# Sheet5.net
KiCad netlist of a schematic drawn in Altium Designer
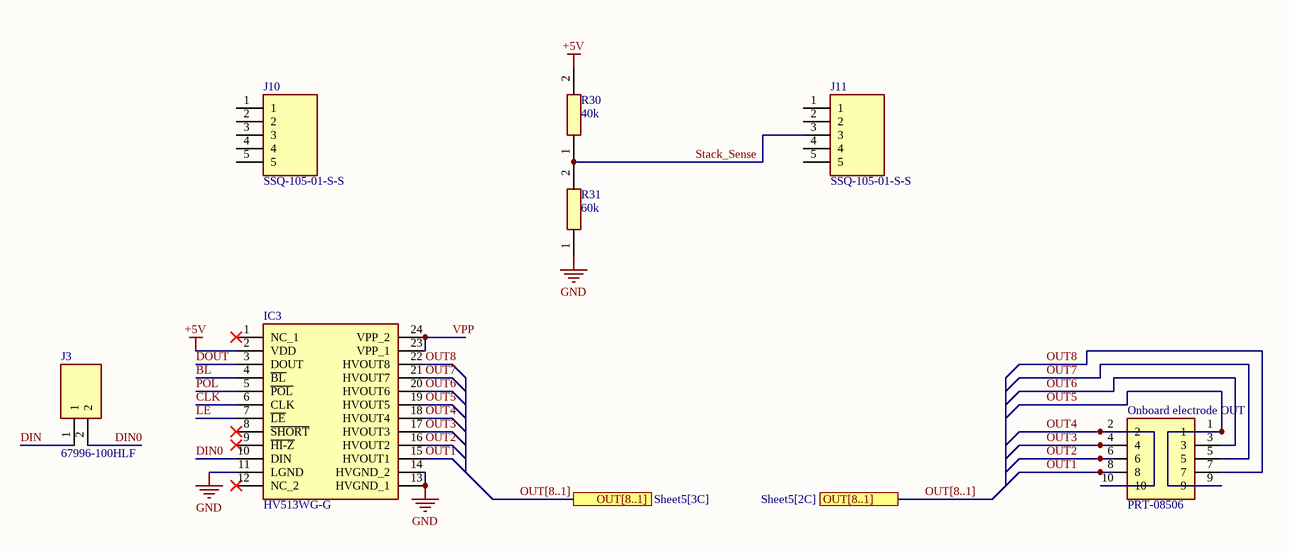
[diagram p0: Sheet5.SchDoc]

(export (version "E")
  (design (tool "Eeschema 10.0.6"))
  (components
    (comp (ref "IC3")
      (value "HV513WG-G")
      (footprint "SamacSys:SOIC127P1030X265-24N")
      (description "Integrated Circuit")
      (fields (field (name "MOUSER PART NUMBER") "689-HV513WG-G"))
      (libsource (lib "*") (part "HV513WG-G"))
    )
    (comp (ref "J3")
      (value "67996-100HLF")
      (footprint "HDRV2W67P254_2X1_254X483X858P")
      (libsource (lib "67996-100HLF") (part "67996-100HLF"))
    )
    (comp (ref "J10")
      (value "SSQ-105-01-S-S")
      (footprint "RHDR5W64P254_1X5_1321X241X851P")
      (description "5 Position, .100&quot; Tiger Buy&trade; Socket Strip, Square Tail, Single Row")
      (fields (field (name "MOUSER PART NUMBER") "200-SSQ10501SS"))
      (libsource (lib "SSQ-105-01-S-S") (part "SSQ-105-01-S-S"))
    )
    (comp (ref "J11")
      (value "SSQ-105-01-S-S")
      (footprint "RHDR5W64P254_1X5_1321X241X851P")
      (description "5 Position, .100&quot; Tiger Buy&trade; Socket Strip, Square Tail, Single Row")
      (fields (field (name "MOUSER PART NUMBER") "200-SSQ10501SS"))
      (libsource (lib "SSQ-105-01-S-S") (part "SSQ-105-01-S-S"))
    )
    (comp (ref "Onboard electrode OUT")
      (value "PRT-08506")
      (footprint "SamacSys:SHDR10W64P254_2X5_2025X900X935P")
      (description "Connector")
      (fields (field (name "MOUSER PART NUMBER") "474-PRT-08506"))
      (libsource (lib "*") (part "PRT-08506"))
    )
    (comp (ref "R30")
      (value "40k")
      (footprint "SamacSys:ERJP06D1000V")
      (description "Resistor")
      (fields
        (field (name "MANUFACTURER_PART_NUMBER") "ERJ-P06F5103V")
        (field (name "MOUSER PART NUMBER") "667-ERJ-P06F5103V")
      )
      (libsource (lib "SamacSys") (part "ERJ-P06F5103V"))
    )
    (comp (ref "R31")
      (value "60k")
      (footprint "SamacSys:ERJP06D1000V")
      (description "Resistor")
      (fields
        (field (name "MANUFACTURER_PART_NUMBER") "ERJ-P06F5103V")
        (field (name "MOUSER PART NUMBER") "667-ERJ-P06F5103V")
      )
      (libsource (lib "SamacSys") (part "ERJ-P06F5103V"))
    )
  )
  (nets
    (net (code "1") (name "+5V") (class "Default")
      (node (ref "IC3") (pin "2") (pinfunction "VDD_2") (pintype "passive"))
      (node (ref "R30") (pin "2") (pinfunction "2_2") (pintype "passive"))
    )
    (net (code "2") (name "/BL") (class "Default")
      (node (ref "IC3") (pin "4") (pinfunction "~{BL}_4") (pintype "passive"))
    )
    (net (code "3") (name "/CLK") (class "Default")
      (node (ref "IC3") (pin "6") (pinfunction "CLK_6") (pintype "passive"))
    )
    (net (code "4") (name "/DIN") (class "Default")
      (node (ref "J3") (pin "1") (pinfunction "1_1") (pintype "passive"))
    )
    (net (code "5") (name "/DIN0") (class "Default")
      (node (ref "IC3") (pin "10") (pinfunction "DIN_10") (pintype "passive"))
      (node (ref "J3") (pin "2") (pinfunction "2_2") (pintype "passive"))
    )
    (net (code "6") (name "/DOUT") (class "Default")
      (node (ref "IC3") (pin "3") (pinfunction "DOUT_3") (pintype "passive"))
    )
    (net (code "7") (name "/LE") (class "Default")
      (node (ref "IC3") (pin "7") (pinfunction "~{LE}_7") (pintype "passive"))
    )
    (net (code "8") (name "/OUT1") (class "Default")
      (node (ref "IC3") (pin "15") (pinfunction "HVOUT1_15") (pintype "passive"))
      (node (ref "Onboard electrode OUT") (pin "8") (pinfunction "8_8") (pintype "passive"))
    )
    (net (code "9") (name "/OUT2") (class "Default")
      (node (ref "IC3") (pin "16") (pinfunction "HVOUT2_16") (pintype "passive"))
      (node (ref "Onboard electrode OUT") (pin "6") (pinfunction "6_6") (pintype "passive"))
    )
    (net (code "10") (name "/OUT3") (class "Default")
      (node (ref "IC3") (pin "17") (pinfunction "HVOUT3_17") (pintype "passive"))
      (node (ref "Onboard electrode OUT") (pin "4") (pinfunction "4_4") (pintype "passive"))
    )
    (net (code "11") (name "/OUT4") (class "Default")
      (node (ref "IC3") (pin "18") (pinfunction "HVOUT4_18") (pintype "passive"))
      (node (ref "Onboard electrode OUT") (pin "10") (pinfunction "10_10") (pintype "passive"))
      (node (ref "Onboard electrode OUT") (pin "2") (pinfunction "2_2") (pintype "passive"))
    )
    (net (code "12") (name "/OUT5") (class "Default")
      (node (ref "IC3") (pin "19") (pinfunction "HVOUT5_19") (pintype "passive"))
      (node (ref "Onboard electrode OUT") (pin "1") (pinfunction "1_1") (pintype "passive"))
      (node (ref "Onboard electrode OUT") (pin "9") (pinfunction "9_9") (pintype "passive"))
    )
    (net (code "13") (name "/OUT6") (class "Default")
      (node (ref "IC3") (pin "20") (pinfunction "HVOUT6_20") (pintype "passive"))
      (node (ref "Onboard electrode OUT") (pin "3") (pinfunction "3_3") (pintype "passive"))
    )
    (net (code "14") (name "/OUT7") (class "Default")
      (node (ref "IC3") (pin "21") (pinfunction "HVOUT7_21") (pintype "passive"))
      (node (ref "Onboard electrode OUT") (pin "5") (pinfunction "5_5") (pintype "passive"))
    )
    (net (code "15") (name "/OUT8") (class "Default")
      (node (ref "IC3") (pin "22") (pinfunction "HVOUT8_22") (pintype "passive"))
      (node (ref "Onboard electrode OUT") (pin "7") (pinfunction "7_7") (pintype "passive"))
    )
    (net (code "17") (name "/POL") (class "Default")
      (node (ref "IC3") (pin "5") (pinfunction "~{POL}_5") (pintype "passive"))
    )
    (net (code "18") (name "/Stack_Sense") (class "Default")
      (node (ref "J11") (pin "3") (pinfunction "3_3") (pintype "passive"))
      (node (ref "R30") (pin "1") (pinfunction "1_1") (pintype "passive"))
      (node (ref "R31") (pin "2") (pinfunction "2_2") (pintype "passive"))
    )
    (net (code "19") (name "/VPP") (class "Default")
      (node (ref "IC3") (pin "23") (pinfunction "VPP_1_23") (pintype "passive"))
      (node (ref "IC3") (pin "24") (pinfunction "VPP_2_24") (pintype "passive"))
    )
    (net (code "20") (name "GND") (class "Default")
      (node (ref "IC3") (pin "11") (pinfunction "LGND_11") (pintype "passive"))
      (node (ref "IC3") (pin "13") (pinfunction "HVGND_1_13") (pintype "passive"))
      (node (ref "IC3") (pin "14") (pinfunction "HVGND_2_14") (pintype "passive"))
      (node (ref "R31") (pin "1") (pinfunction "1_1") (pintype "passive"))
    )
    (net (code "21") (name "unconnected-(IC3-NC_1-Pad1)") (class "Default")
      (node (ref "IC3") (pin "1") (pinfunction "NC_1_1") (pintype "passive+no_connect"))
    )
    (net (code "22") (name "unconnected-(IC3-NC_2-Pad12)") (class "Default")
      (node (ref "IC3") (pin "12") (pinfunction "NC_2_12") (pintype "passive+no_connect"))
    )
    (net (code "23") (name "unconnected-(IC3-~{HI-Z}-Pad9)") (class "Default")
      (node (ref "IC3") (pin "9") (pinfunction "~{HI-Z}_9") (pintype "passive+no_connect"))
    )
    (net (code "24") (name "unconnected-(IC3-~{SHORT}-Pad8)") (class "Default")
      (node (ref "IC3") (pin "8") (pinfunction "~{SHORT}_8") (pintype "passive+no_connect"))
    )
    (net (code "25") (name "unconnected-(J10-Pad1)") (class "Default")
      (node (ref "J10") (pin "1") (pinfunction "1_1") (pintype "passive"))
    )
    (net (code "26") (name "unconnected-(J10-Pad2)") (class "Default")
      (node (ref "J10") (pin "2") (pinfunction "2_2") (pintype "passive"))
    )
    (net (code "27") (name "unconnected-(J10-Pad3)") (class "Default")
      (node (ref "J10") (pin "3") (pinfunction "3_3") (pintype "passive"))
    )
    (net (code "28") (name "unconnected-(J10-Pad4)") (class "Default")
      (node (ref "J10") (pin "4") (pinfunction "4_4") (pintype "passive"))
    )
    (net (code "29") (name "unconnected-(J10-Pad5)") (class "Default")
      (node (ref "J10") (pin "5") (pinfunction "5_5") (pintype "passive"))
    )
    (net (code "30") (name "unconnected-(J11-Pad1)") (class "Default")
      (node (ref "J11") (pin "1") (pinfunction "1_1") (pintype "passive"))
    )
    (net (code "31") (name "unconnected-(J11-Pad2)") (class "Default")
      (node (ref "J11") (pin "2") (pinfunction "2_2") (pintype "passive"))
    )
    (net (code "32") (name "unconnected-(J11-Pad4)") (class "Default")
      (node (ref "J11") (pin "4") (pinfunction "4_4") (pintype "passive"))
    )
    (net (code "33") (name "unconnected-(J11-Pad5)") (class "Default")
      (node (ref "J11") (pin "5") (pinfunction "5_5") (pintype "passive"))
    )
  )
)
